# vin-5v-regulator.net
KiCad netlist of a schematic drawn in EAGLE
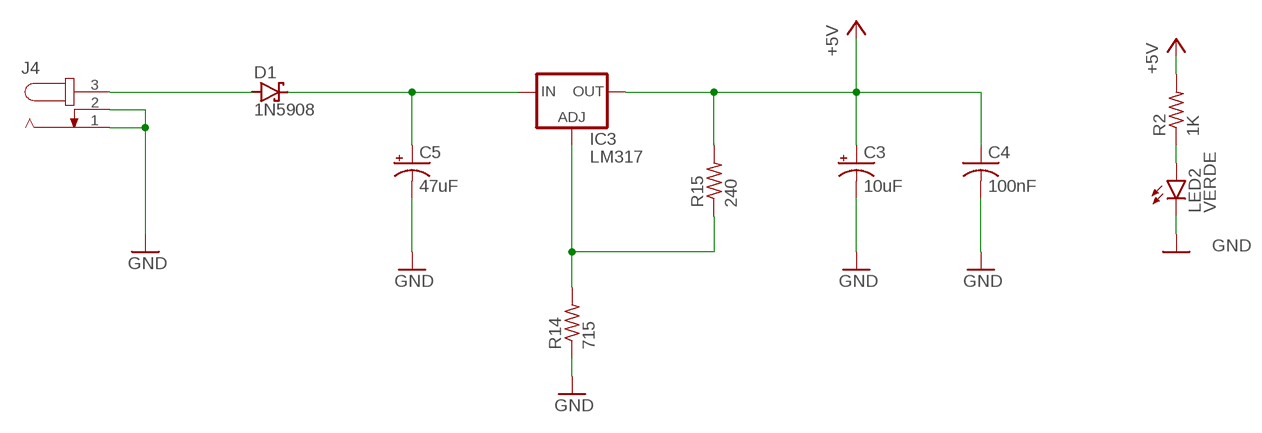
[diagram p0: schematic, sheet 1]

(export (version "E")
  (design (tool "Eeschema 10.0.6"))
  (components
    (comp (ref "C3")
      (value "10uF")
      (footprint "eagle-import:E2,5-6E")
      (libsource (lib "eagle-import") (part "CPOL-USE2,5-6E"))
    )
    (comp (ref "C4")
      (value "100nF")
      (footprint "eagle-import:C025-030X050")
      (libsource (lib "eagle-import") (part "C-US025-030X050"))
    )
    (comp (ref "C5")
      (value "47uF")
      (footprint "eagle-import:E2,5-6E")
      (libsource (lib "eagle-import") (part "CPOL-USE2,5-6E"))
    )
    (comp (ref "D1")
      (value "1N5908")
      (footprint "eagle-import:C4111-15")
      (libsource (lib "eagle-import") (part "1N5908"))
    )
    (comp (ref "IC3")
      (value "LM317")
      (footprint "eagle-import:317TS")
      (libsource (lib "eagle-import") (part "LM317TS"))
    )
    (comp (ref "J4")
      (value "JACK-PLUG0")
      (footprint "eagle-import:SPC4077")
      (libsource (lib "eagle-import") (part "JACK-PLUG0"))
    )
    (comp (ref "LED2")
      (value "VERDE")
      (footprint "eagle-import:LED5MM")
      (libsource (lib "eagle-import") (part "LED5MM"))
    )
    (comp (ref "R2")
      (value "1K")
      (footprint "eagle-import:0207_10")
      (libsource (lib "eagle-import") (part "R-US_0207/10"))
    )
    (comp (ref "R14")
      (value "715")
      (footprint "eagle-import:0207_10")
      (libsource (lib "eagle-import") (part "R-US_0207/10"))
    )
    (comp (ref "R15")
      (value "240")
      (footprint "eagle-import:0207_10")
      (libsource (lib "eagle-import") (part "R-US_0207/10"))
    )
  )
  (nets
    (net (code "1") (name "+5V") (class "Default")
      (node (ref "C3") (pin "+") (pinfunction "+_+") (pintype "passive"))
      (node (ref "C4") (pin "1") (pinfunction "1_1") (pintype "passive"))
      (node (ref "IC3") (pin "2") (pinfunction "OUT_2") (pintype "passive"))
      (node (ref "R15") (pin "2") (pinfunction "2_2") (pintype "passive"))
      (node (ref "R2") (pin "2") (pinfunction "2_2") (pintype "passive"))
    )
    (net (code "2") (name "GND") (class "Default")
      (node (ref "C3") (pin "-") (pinfunction "-_-") (pintype "passive"))
      (node (ref "C4") (pin "2") (pinfunction "2_2") (pintype "passive"))
      (node (ref "C5") (pin "-") (pinfunction "-_-") (pintype "passive"))
      (node (ref "J4") (pin "1") (pinfunction "1_1") (pintype "passive"))
      (node (ref "J4") (pin "2") (pinfunction "2_2") (pintype "passive"))
      (node (ref "LED2") (pin "K") (pinfunction "C_K") (pintype "passive"))
      (node (ref "R14") (pin "1") (pinfunction "1_1") (pintype "passive"))
    )
    (net (code "3") (name "Net-(D1-PadA)") (class "Default")
      (node (ref "D1") (pin "A") (pinfunction "A_A") (pintype "passive"))
      (node (ref "J4") (pin "3") (pinfunction "3_3") (pintype "passive"))
    )
    (net (code "4") (name "Net-(IC3-ADJ)") (class "Default")
      (node (ref "IC3") (pin "1") (pinfunction "ADJ_1") (pintype "input"))
      (node (ref "R14") (pin "2") (pinfunction "2_2") (pintype "passive"))
      (node (ref "R15") (pin "1") (pinfunction "1_1") (pintype "passive"))
    )
    (net (code "5") (name "Net-(IC3-IN)") (class "Default")
      (node (ref "C5") (pin "+") (pinfunction "+_+") (pintype "passive"))
      (node (ref "D1") (pin "C") (pinfunction "C_C") (pintype "passive"))
      (node (ref "IC3") (pin "3") (pinfunction "IN_3") (pintype "input"))
    )
    (net (code "6") (name "Net-(LED2-PadA)") (class "Default")
      (node (ref "LED2") (pin "A") (pinfunction "A_A") (pintype "passive"))
      (node (ref "R2") (pin "1") (pinfunction "1_1") (pintype "passive"))
    )
  )
)
